# 08_FPGA_HSIO_B3.net
KiCad netlist of a schematic drawn in Altium Designer
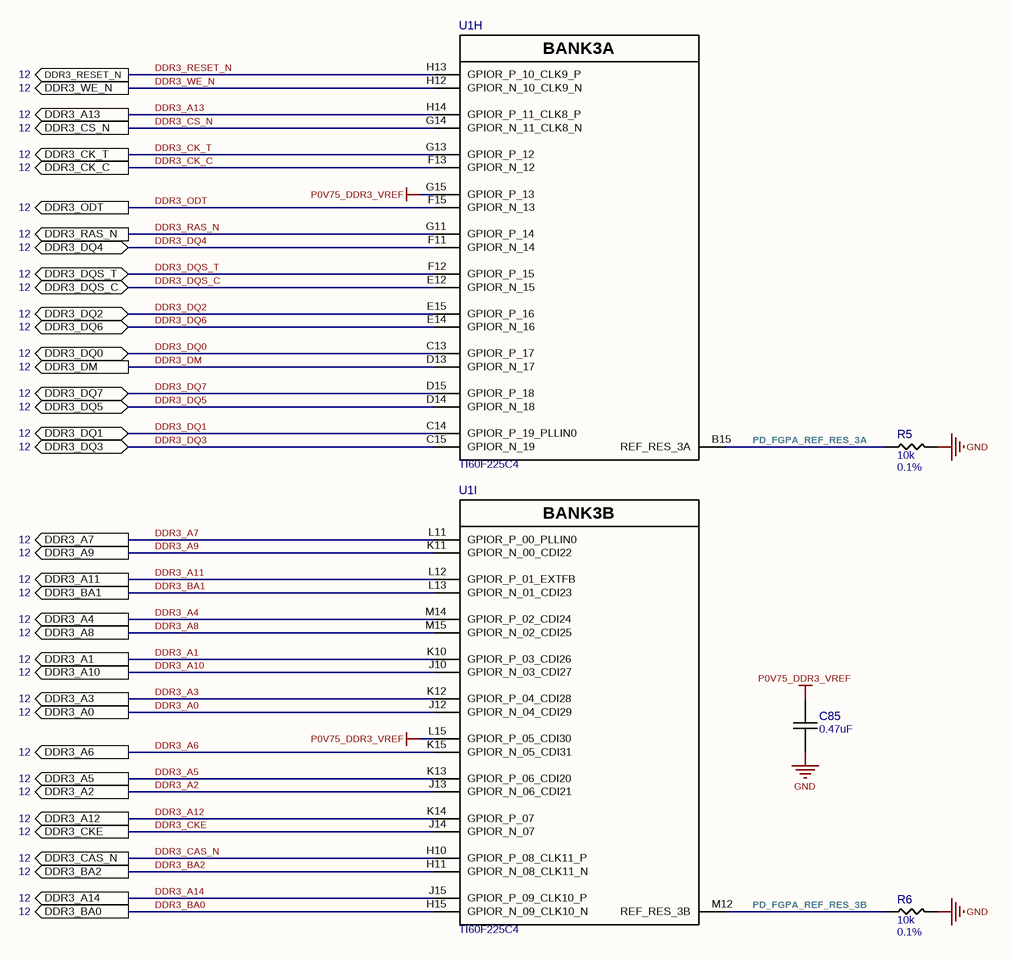
[diagram p0: 08_FPGA_HSIO_B3.SchDoc]

(export (version "E")
  (design (tool "Eeschema 10.0.6"))
  (components
    (comp (ref "C85")
      (value "0.47uF")
      (footprint "CAPC0603X03N")
      (description "CAP CER 0.47UF 6.3V X5R 0201")
      (fields (field (name "PART NUMBER") "GRM033R60J474KE90D") (field (name "VOLTAGE") "6.3V"))
      (libsource (lib "Database") (part "Capacitor"))
    )
    (comp (ref "R5")
      (value "10k")
      (footprint "RESC1005X03N")
      (description "RES SMD 10K OHM 0.1% 1/16W 0402")
      (fields (field (name "PART NUMBER") "RT0402BRD0710KL") (field (name "TOL") "0.1%"))
      (libsource (lib "Database") (part "Resistor_ENG"))
    )
    (comp (ref "R6")
      (value "10k")
      (footprint "RESC1005X03N")
      (description "RES SMD 10K OHM 0.1% 1/16W 0402")
      (fields (field (name "PART NUMBER") "RT0402BRD0710KL") (field (name "TOL") "0.1%"))
      (libsource (lib "Database") (part "Resistor_ENG"))
    )
    (comp (ref "U1")
      (value "TI60F225C4")
      (footprint "BGA225C65P15X15_1000X1000X100")
      (description "FPGA TITAN 140HSIO 4PLL 225BGA")
      (libsource (lib "Database") (part "TI60F225"))
    )
  )
  (nets
    (net (code "1") (name "/DDR3_A0") (class "Default")
      (node (ref "U1") (pin "J12") (pinfunction "GPIOR_N_04_CDI29_J12") (pintype "passive"))
    )
    (net (code "2") (name "/DDR3_A1") (class "Default")
      (node (ref "U1") (pin "K10") (pinfunction "GPIOR_P_03_CDI26_K10") (pintype "passive"))
    )
    (net (code "3") (name "/DDR3_A2") (class "Default")
      (node (ref "U1") (pin "J13") (pinfunction "GPIOR_N_06_CDI21_J13") (pintype "passive"))
    )
    (net (code "4") (name "/DDR3_A3") (class "Default")
      (node (ref "U1") (pin "K12") (pinfunction "GPIOR_P_04_CDI28_K12") (pintype "passive"))
    )
    (net (code "5") (name "/DDR3_A4") (class "Default")
      (node (ref "U1") (pin "M14") (pinfunction "GPIOR_P_02_CDI24_M14") (pintype "passive"))
    )
    (net (code "6") (name "/DDR3_A5") (class "Default")
      (node (ref "U1") (pin "K13") (pinfunction "GPIOR_P_06_CDI20_K13") (pintype "passive"))
    )
    (net (code "7") (name "/DDR3_A6") (class "Default")
      (node (ref "U1") (pin "K15") (pinfunction "GPIOR_N_05_CDI31_K15") (pintype "passive"))
    )
    (net (code "8") (name "/DDR3_A7") (class "Default")
      (node (ref "U1") (pin "L11") (pinfunction "GPIOR_P_00_PLLIN0_L11") (pintype "passive"))
    )
    (net (code "9") (name "/DDR3_A8") (class "Default")
      (node (ref "U1") (pin "M15") (pinfunction "GPIOR_N_02_CDI25_M15") (pintype "passive"))
    )
    (net (code "10") (name "/DDR3_A9") (class "Default")
      (node (ref "U1") (pin "K11") (pinfunction "GPIOR_N_00_CDI22_K11") (pintype "passive"))
    )
    (net (code "11") (name "/DDR3_A10") (class "Default")
      (node (ref "U1") (pin "J10") (pinfunction "GPIOR_N_03_CDI27_J10") (pintype "passive"))
    )
    (net (code "12") (name "/DDR3_A11") (class "Default")
      (node (ref "U1") (pin "L12") (pinfunction "GPIOR_P_01_EXTFB_L12") (pintype "passive"))
    )
    (net (code "13") (name "/DDR3_A12") (class "Default")
      (node (ref "U1") (pin "K14") (pinfunction "GPIOR_P_07_K14") (pintype "passive"))
    )
    (net (code "14") (name "/DDR3_A13") (class "Default")
      (node (ref "U1") (pin "H14") (pinfunction "GPIOR_P_11_CLK8_P_H14") (pintype "passive"))
    )
    (net (code "15") (name "/DDR3_A14") (class "Default")
      (node (ref "U1") (pin "J15") (pinfunction "GPIOR_P_09_CLK10_P_J15") (pintype "passive"))
    )
    (net (code "16") (name "/DDR3_BA0") (class "Default")
      (node (ref "U1") (pin "H15") (pinfunction "GPIOR_N_09_CLK10_N_H15") (pintype "passive"))
    )
    (net (code "17") (name "/DDR3_BA1") (class "Default")
      (node (ref "U1") (pin "L13") (pinfunction "GPIOR_N_01_CDI23_L13") (pintype "passive"))
    )
    (net (code "18") (name "/DDR3_BA2") (class "Default")
      (node (ref "U1") (pin "H11") (pinfunction "GPIOR_N_08_CLK11_N_H11") (pintype "passive"))
    )
    (net (code "19") (name "/DDR3_CAS_N") (class "Default")
      (node (ref "U1") (pin "H10") (pinfunction "GPIOR_P_08_CLK11_P_H10") (pintype "passive"))
    )
    (net (code "20") (name "/DDR3_CKE") (class "Default")
      (node (ref "U1") (pin "J14") (pinfunction "GPIOR_N_07_J14") (pintype "passive"))
    )
    (net (code "21") (name "/DDR3_CK_C") (class "Default")
      (node (ref "U1") (pin "F13") (pinfunction "GPIOR_N_12_F13") (pintype "passive"))
    )
    (net (code "22") (name "/DDR3_CK_T") (class "Default")
      (node (ref "U1") (pin "G13") (pinfunction "GPIOR_P_12_G13") (pintype "passive"))
    )
    (net (code "23") (name "/DDR3_CS_N") (class "Default")
      (node (ref "U1") (pin "G14") (pinfunction "GPIOR_N_11_CLK8_N_G14") (pintype "passive"))
    )
    (net (code "24") (name "/DDR3_DM") (class "Default")
      (node (ref "U1") (pin "D13") (pinfunction "GPIOR_N_17_D13") (pintype "passive"))
    )
    (net (code "25") (name "/DDR3_DQ0") (class "Default")
      (node (ref "U1") (pin "C13") (pinfunction "GPIOR_P_17_C13") (pintype "passive"))
    )
    (net (code "26") (name "/DDR3_DQ1") (class "Default")
      (node (ref "U1") (pin "C14") (pinfunction "GPIOR_P_19_PLLIN0_C14") (pintype "passive"))
    )
    (net (code "27") (name "/DDR3_DQ2") (class "Default")
      (node (ref "U1") (pin "E15") (pinfunction "GPIOR_P_16_E15") (pintype "passive"))
    )
    (net (code "28") (name "/DDR3_DQ3") (class "Default")
      (node (ref "U1") (pin "C15") (pinfunction "GPIOR_N_19_C15") (pintype "passive"))
    )
    (net (code "29") (name "/DDR3_DQ4") (class "Default")
      (node (ref "U1") (pin "F11") (pinfunction "GPIOR_N_14_F11") (pintype "passive"))
    )
    (net (code "30") (name "/DDR3_DQ5") (class "Default")
      (node (ref "U1") (pin "D14") (pinfunction "GPIOR_N_18_D14") (pintype "passive"))
    )
    (net (code "31") (name "/DDR3_DQ6") (class "Default")
      (node (ref "U1") (pin "E14") (pinfunction "GPIOR_N_16_E14") (pintype "passive"))
    )
    (net (code "32") (name "/DDR3_DQ7") (class "Default")
      (node (ref "U1") (pin "D15") (pinfunction "GPIOR_P_18_D15") (pintype "passive"))
    )
    (net (code "33") (name "/DDR3_DQS_C") (class "Default")
      (node (ref "U1") (pin "E12") (pinfunction "GPIOR_N_15_E12") (pintype "passive"))
    )
    (net (code "34") (name "/DDR3_DQS_T") (class "Default")
      (node (ref "U1") (pin "F12") (pinfunction "GPIOR_P_15_F12") (pintype "passive"))
    )
    (net (code "35") (name "/DDR3_ODT") (class "Default")
      (node (ref "U1") (pin "F15") (pinfunction "GPIOR_N_13_F15") (pintype "passive"))
    )
    (net (code "36") (name "/DDR3_RAS_N") (class "Default")
      (node (ref "U1") (pin "G11") (pinfunction "GPIOR_P_14_G11") (pintype "passive"))
    )
    (net (code "37") (name "/DDR3_RESET_N") (class "Default")
      (node (ref "U1") (pin "H13") (pinfunction "GPIOR_P_10_CLK9_P_H13") (pintype "passive"))
    )
    (net (code "38") (name "/DDR3_WE_N") (class "Default")
      (node (ref "U1") (pin "H12") (pinfunction "GPIOR_N_10_CLK9_N_H12") (pintype "passive"))
    )
    (net (code "39") (name "/PD_FGPA_REF_RES_3A") (class "Default")
      (node (ref "R5") (pin "1") (pinfunction "1_1") (pintype "passive"))
      (node (ref "U1") (pin "B15") (pinfunction "REF_RES_3A_B15") (pintype "passive"))
    )
    (net (code "40") (name "/PD_FGPA_REF_RES_3B") (class "Default")
      (node (ref "R6") (pin "1") (pinfunction "1_1") (pintype "passive"))
      (node (ref "U1") (pin "M12") (pinfunction "REF_RES_3B_M12") (pintype "passive"))
    )
    (net (code "41") (name "GND") (class "Default")
      (node (ref "C85") (pin "1") (pinfunction "1_1") (pintype "passive"))
      (node (ref "R5") (pin "2") (pinfunction "2_2") (pintype "passive"))
      (node (ref "R6") (pin "2") (pinfunction "2_2") (pintype "passive"))
    )
    (net (code "42") (name "P0V75_DDR3_VREF") (class "Default")
      (node (ref "C85") (pin "2") (pinfunction "2_2") (pintype "passive"))
      (node (ref "U1") (pin "G15") (pinfunction "GPIOR_P_13_G15") (pintype "passive"))
      (node (ref "U1") (pin "L15") (pinfunction "GPIOR_P_05_CDI30_L15") (pintype "passive"))
    )
  )
)
